# audio-amp.net
KiCad netlist of a schematic drawn in EAGLE
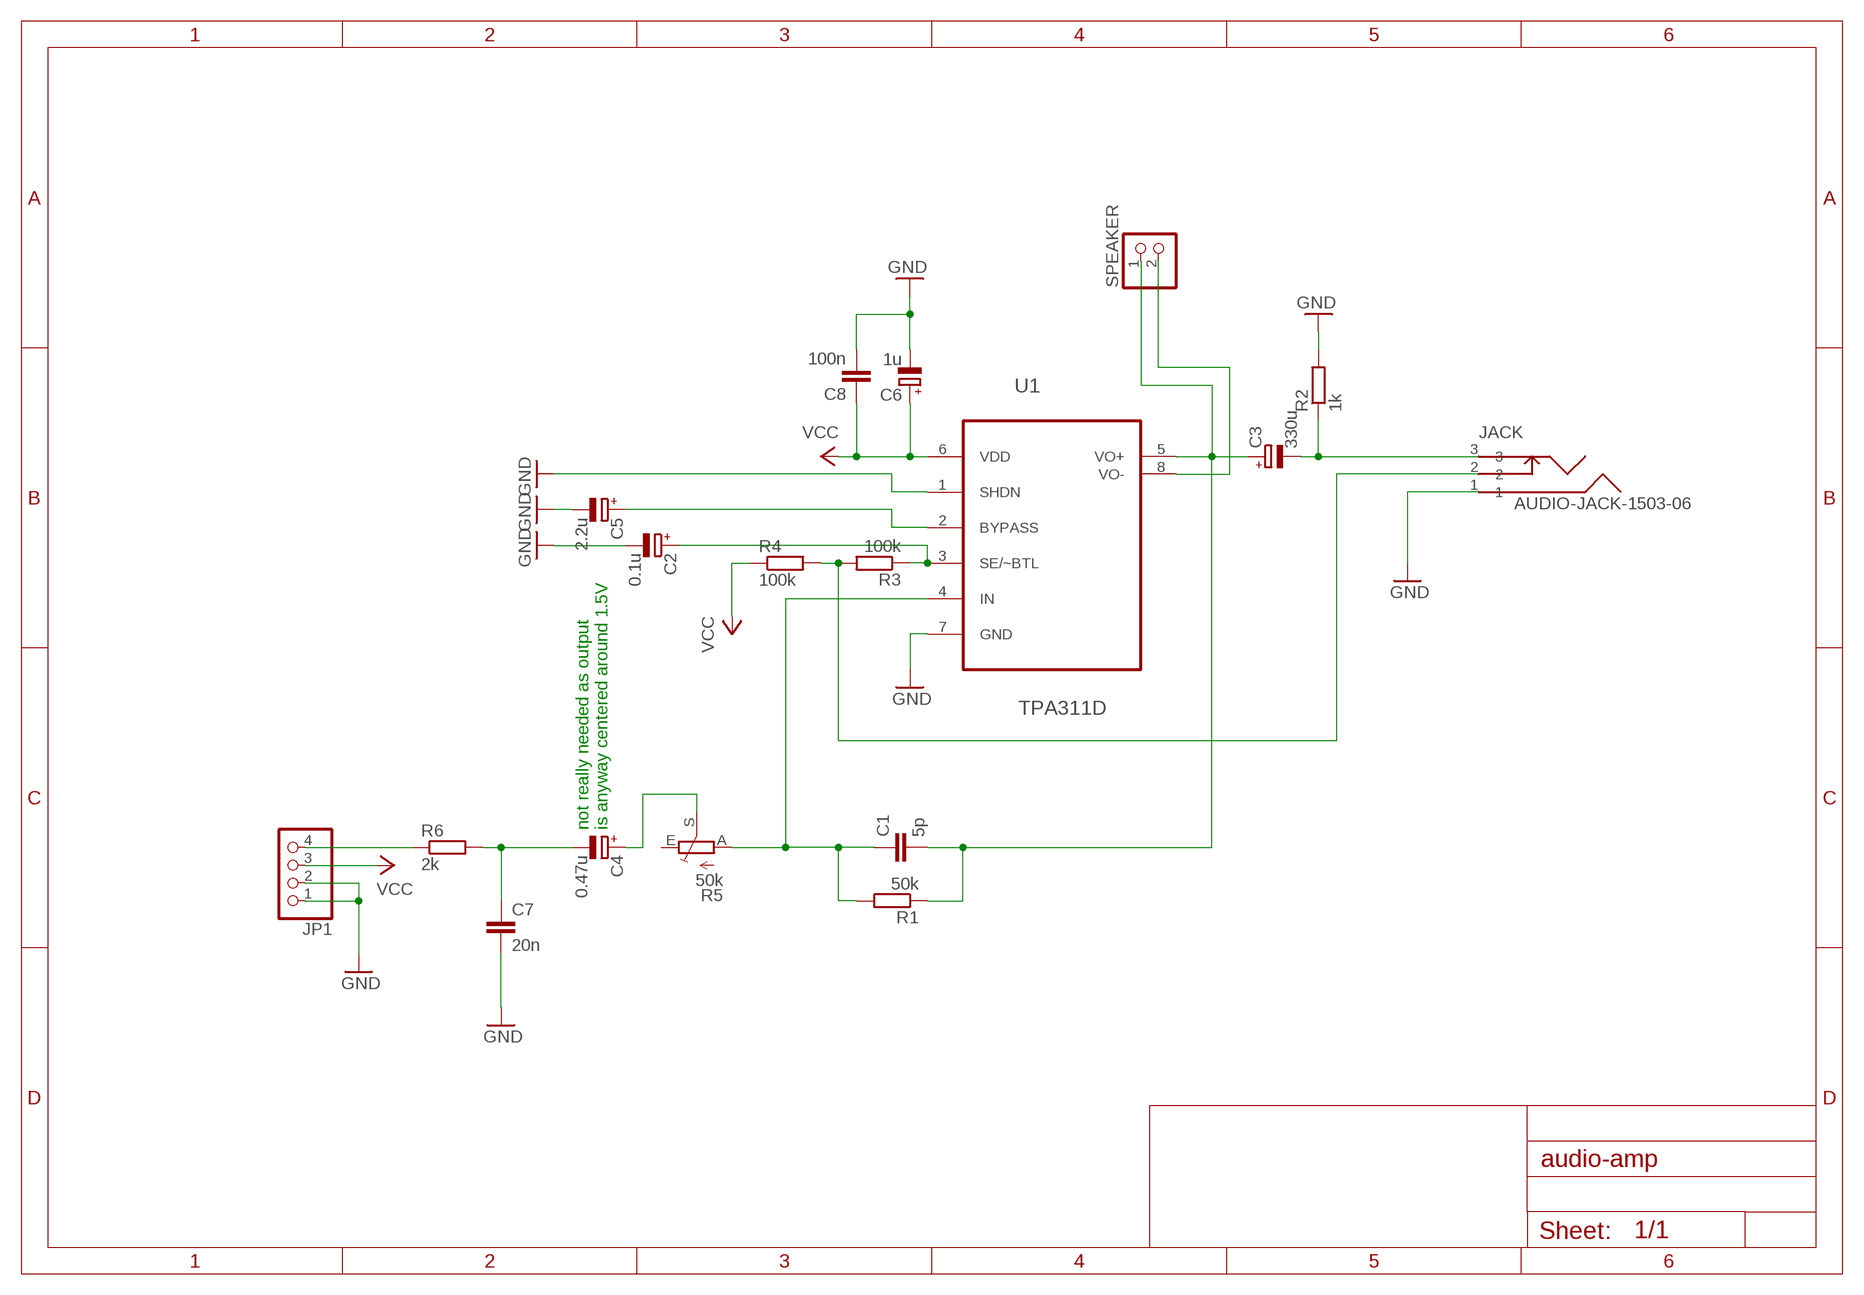
[diagram p0: schematic, sheet 1]

(export (version "E")
  (design (tool "Eeschema 10.0.6"))
  (components
    (comp (ref "C1")
      (value "5p")
      (footprint "eagle-import:C0805")
      (libsource (lib "eagle-import") (part "C-EUC0805"))
    )
    (comp (ref "C2")
      (value "0.1u")
      (footprint "eagle-import:E2-5")
      (libsource (lib "eagle-import") (part "CPOL-EUE2-5"))
    )
    (comp (ref "C3")
      (value "330u")
      (footprint "eagle-import:E2-5")
      (libsource (lib "eagle-import") (part "CPOL-EUE2-5"))
    )
    (comp (ref "C4")
      (value "0.47u")
      (footprint "eagle-import:E2-5")
      (libsource (lib "eagle-import") (part "CPOL-EUE2-5"))
    )
    (comp (ref "C5")
      (value "2.2u")
      (footprint "eagle-import:E2-5")
      (libsource (lib "eagle-import") (part "CPOL-EUE2-5"))
    )
    (comp (ref "C6")
      (value "1u")
      (footprint "eagle-import:E2-5")
      (libsource (lib "eagle-import") (part "CPOL-EUE2-5"))
    )
    (comp (ref "C7")
      (value "20n")
      (footprint "eagle-import:C0805")
      (libsource (lib "eagle-import") (part "C-EUC0805"))
    )
    (comp (ref "C8")
      (value "100n")
      (footprint "eagle-import:C0805")
      (libsource (lib "eagle-import") (part "C-EUC0805"))
    )
    (comp (ref "JACK")
      (value "AUDIO-JACK-1503-06")
      (footprint "eagle-import:AUDIO-JACK")
      (libsource (lib "eagle-import") (part "AUDIO-JACK-1503-06"))
    )
    (comp (ref "JP1")
      (value "PINHD-1X4")
      (footprint "eagle-import:1X04")
      (libsource (lib "eagle-import") (part "PINHD-1X4"))
    )
    (comp (ref "R1")
      (value "50k")
      (footprint "eagle-import:R0805")
      (libsource (lib "eagle-import") (part "R-EU_R0805"))
    )
    (comp (ref "R2")
      (value "1k")
      (footprint "eagle-import:R0805")
      (libsource (lib "eagle-import") (part "R-EU_R0805"))
    )
    (comp (ref "R3")
      (value "100k")
      (footprint "eagle-import:R0805")
      (libsource (lib "eagle-import") (part "R-EU_R0805"))
    )
    (comp (ref "R4")
      (value "100k")
      (footprint "eagle-import:R0805")
      (libsource (lib "eagle-import") (part "R-EU_R0805"))
    )
    (comp (ref "R5")
      (value "50k")
      (footprint "eagle-import:PT-10")
      (libsource (lib "eagle-import") (part "TRIM_EU-PT10"))
    )
    (comp (ref "R6")
      (value "2k")
      (footprint "eagle-import:R0805")
      (libsource (lib "eagle-import") (part "R-EU_R0805"))
    )
    (comp (ref "SPEAKER")
      (value "PINHD-1X2")
      (footprint "eagle-import:1X02")
      (libsource (lib "eagle-import") (part "PINHD-1X2"))
    )
    (comp (ref "U1")
      (value "TPA311D")
      (footprint "eagle-import:SOIC127P600X175-8N")
      (libsource (lib "eagle-import") (part "TPA311D"))
    )
  )
  (nets
    (net (code "1") (name "GND") (class "Default")
      (node (ref "C2") (pin "-") (pinfunction "-_-") (pintype "passive"))
      (node (ref "C5") (pin "-") (pinfunction "-_-") (pintype "passive"))
      (node (ref "C6") (pin "-") (pinfunction "-_-") (pintype "passive"))
      (node (ref "C7") (pin "2") (pinfunction "2_2") (pintype "passive"))
      (node (ref "C8") (pin "2") (pinfunction "2_2") (pintype "passive"))
      (node (ref "JACK") (pin "1") (pinfunction "1_1") (pintype "bidirectional"))
      (node (ref "JP1") (pin "1") (pinfunction "1_1") (pintype "passive"))
      (node (ref "JP1") (pin "2") (pinfunction "2_2") (pintype "passive"))
      (node (ref "R2") (pin "2") (pinfunction "2_2") (pintype "passive"))
      (node (ref "U1") (pin "1") (pinfunction "SHDN_1") (pintype "input"))
      (node (ref "U1") (pin "7") (pinfunction "GND_7") (pintype "passive"))
    )
    (net (code "2") (name "Net-(C3-Pad-)") (class "Default")
      (node (ref "C3") (pin "-") (pinfunction "-_-") (pintype "passive"))
      (node (ref "JACK") (pin "3") (pinfunction "3_3") (pintype "bidirectional"))
      (node (ref "R2") (pin "1") (pinfunction "1_1") (pintype "passive"))
    )
    (net (code "3") (name "Net-(C4-Pad+)") (class "Default")
      (node (ref "C4") (pin "+") (pinfunction "+_+") (pintype "passive"))
      (node (ref "R5") (pin "S") (pinfunction "S_S") (pintype "passive"))
    )
    (net (code "4") (name "Net-(C4-Pad-)") (class "Default")
      (node (ref "C4") (pin "-") (pinfunction "-_-") (pintype "passive"))
      (node (ref "C7") (pin "1") (pinfunction "1_1") (pintype "passive"))
      (node (ref "R6") (pin "2") (pinfunction "2_2") (pintype "passive"))
    )
    (net (code "5") (name "Net-(JACK-Pad2)") (class "Default")
      (node (ref "JACK") (pin "2") (pinfunction "2_2") (pintype "bidirectional"))
      (node (ref "R3") (pin "2") (pinfunction "2_2") (pintype "passive"))
      (node (ref "R4") (pin "2") (pinfunction "2_2") (pintype "passive"))
    )
    (net (code "6") (name "Net-(JP1-Pad4)") (class "Default")
      (node (ref "JP1") (pin "4") (pinfunction "4_4") (pintype "passive"))
      (node (ref "R6") (pin "1") (pinfunction "1_1") (pintype "passive"))
    )
    (net (code "7") (name "Net-(U1-BYPASS)") (class "Default")
      (node (ref "C5") (pin "+") (pinfunction "+_+") (pintype "passive"))
      (node (ref "U1") (pin "2") (pinfunction "BYPASS_2") (pintype "input"))
    )
    (net (code "8") (name "Net-(U1-IN)") (class "Default")
      (node (ref "C1") (pin "1") (pinfunction "1_1") (pintype "passive"))
      (node (ref "R1") (pin "2") (pinfunction "2_2") (pintype "passive"))
      (node (ref "R5") (pin "A") (pinfunction "A_A") (pintype "passive"))
      (node (ref "U1") (pin "4") (pinfunction "IN_4") (pintype "input"))
    )
    (net (code "9") (name "Net-(U1-SE{slash}~{BTL})") (class "Default")
      (node (ref "C2") (pin "+") (pinfunction "+_+") (pintype "passive"))
      (node (ref "R3") (pin "1") (pinfunction "1_1") (pintype "passive"))
      (node (ref "U1") (pin "3") (pinfunction "SE/~{BTL}_3") (pintype "input"))
    )
    (net (code "10") (name "Net-(U1-VO+)") (class "Default")
      (node (ref "C1") (pin "2") (pinfunction "2_2") (pintype "passive"))
      (node (ref "C3") (pin "+") (pinfunction "+_+") (pintype "passive"))
      (node (ref "R1") (pin "1") (pinfunction "1_1") (pintype "passive"))
      (node (ref "SPEAKER") (pin "1") (pinfunction "1_1") (pintype "passive"))
      (node (ref "U1") (pin "5") (pinfunction "VO+_5") (pintype "output"))
    )
    (net (code "11") (name "Net-(U1-VO-)") (class "Default")
      (node (ref "SPEAKER") (pin "2") (pinfunction "2_2") (pintype "passive"))
      (node (ref "U1") (pin "8") (pinfunction "VO-_8") (pintype "output"))
    )
    (net (code "12") (name "VCC") (class "Default")
      (node (ref "C6") (pin "+") (pinfunction "+_+") (pintype "passive"))
      (node (ref "C8") (pin "1") (pinfunction "1_1") (pintype "passive"))
      (node (ref "JP1") (pin "3") (pinfunction "3_3") (pintype "passive"))
      (node (ref "R4") (pin "1") (pinfunction "1_1") (pintype "passive"))
      (node (ref "U1") (pin "6") (pinfunction "VDD_6") (pintype "power_in"))
    )
    (net (code "13") (name "unconnected-(R5-PadE)") (class "Default")
      (node (ref "R5") (pin "E") (pinfunction "E_E") (pintype "passive"))
    )
  )
)
